# remote_unit_phase_3.net
KiCad netlist of a schematic drawn in EAGLE
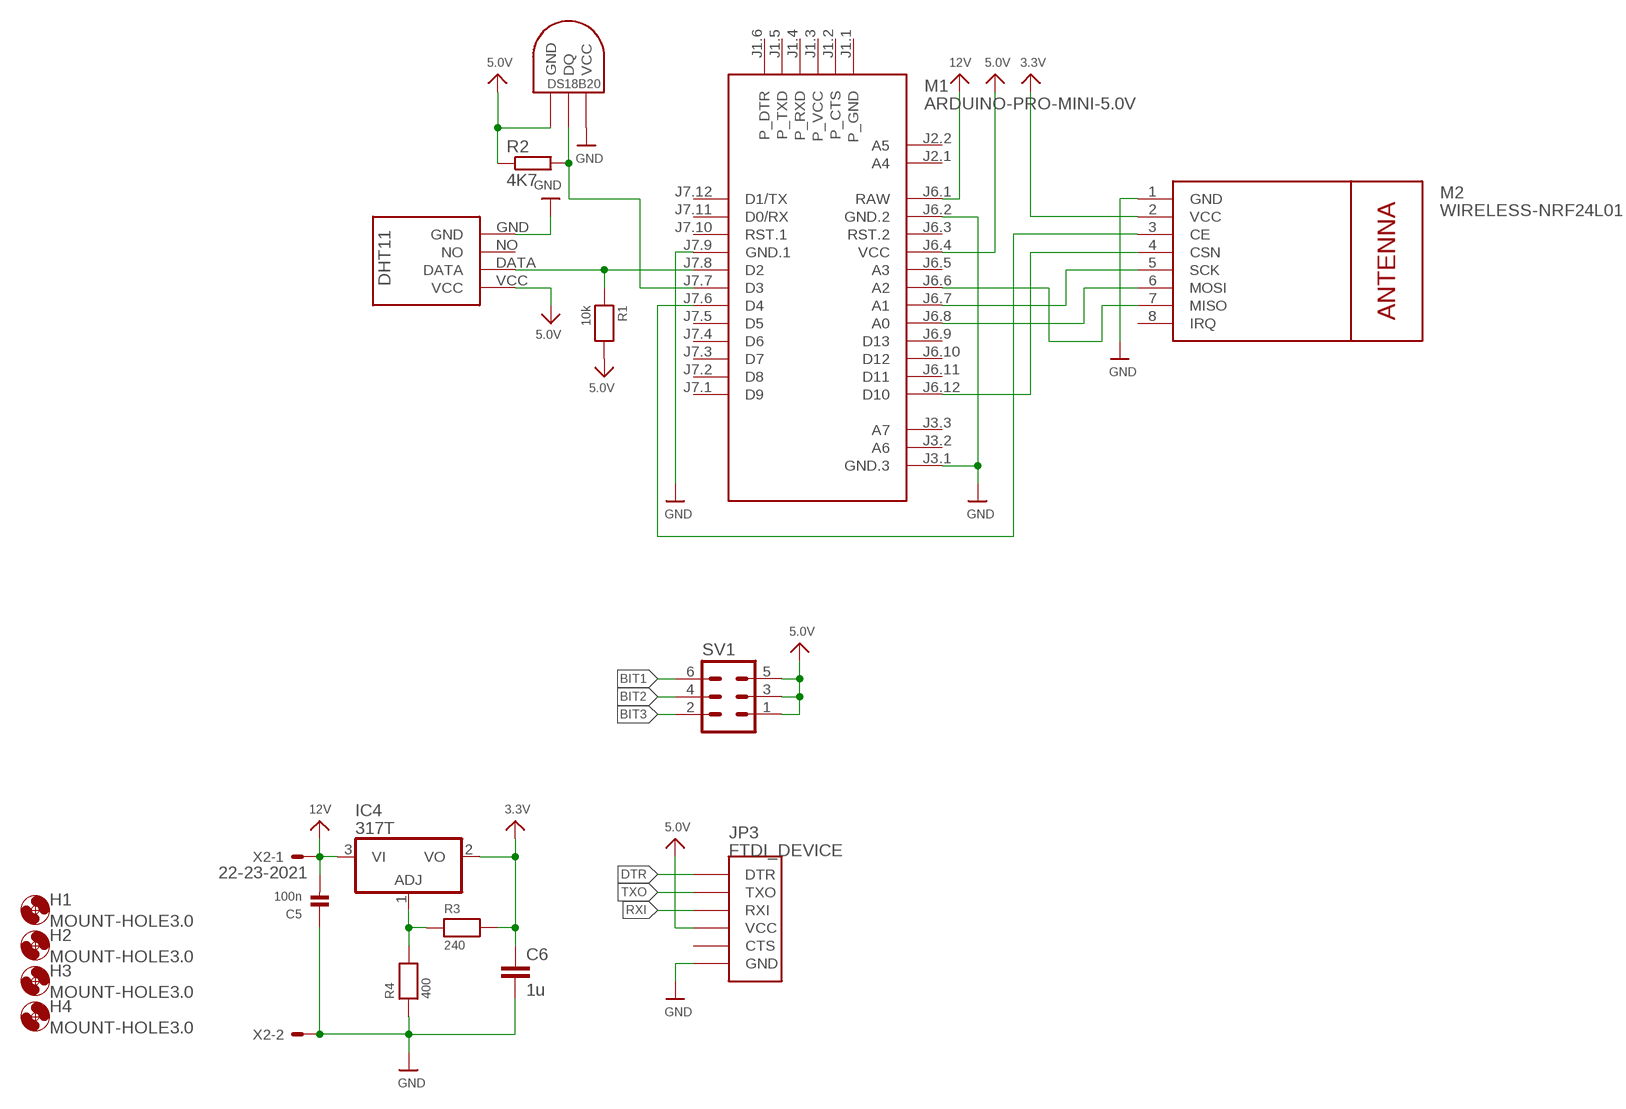
[diagram p0: schematic, sheet 1]

(export (version "E")
  (design (tool "Eeschema 10.0.6"))
  (components
    (comp (ref "C5")
      (value "100n")
      (footprint "eagle-import:_0603")
      (libsource (lib "eagle-import") (part "CAP_CERAMIC_0603"))
    )
    (comp (ref "C6")
      (value "1u")
      (footprint "eagle-import:C050-035X075")
      (libsource (lib "eagle-import") (part "C-EU050-035X075"))
    )
    (comp (ref "H1")
      (value "MOUNT-HOLE3.0")
      (footprint "eagle-import:3,0")
      (libsource (lib "eagle-import") (part "MOUNT-HOLE3.0"))
    )
    (comp (ref "H2")
      (value "MOUNT-HOLE3.0")
      (footprint "eagle-import:3,0")
      (libsource (lib "eagle-import") (part "MOUNT-HOLE3.0"))
    )
    (comp (ref "H3")
      (value "MOUNT-HOLE3.0")
      (footprint "eagle-import:3,0")
      (libsource (lib "eagle-import") (part "MOUNT-HOLE3.0"))
    )
    (comp (ref "H4")
      (value "MOUNT-HOLE3.0")
      (footprint "eagle-import:3,0")
      (libsource (lib "eagle-import") (part "MOUNT-HOLE3.0"))
    )
    (comp (ref "IC4")
      (value "317T")
      (footprint "eagle-import:TO220H")
      (libsource (lib "eagle-import") (part "317T"))
    )
    (comp (ref "JP3")
      (value "FTDI_DEVICE")
      (footprint "eagle-import:FTDI_DEVICE_SIDE")
      (libsource (lib "eagle-import") (part "FTDI_DEVICE"))
    )
    (comp (ref "M1")
      (value "ARDUINO-PRO-MINI-5.0V")
      (footprint "eagle-import:ARDUINO-PRO-MINI")
      (libsource (lib "eagle-import") (part "ARDUINO-PRO-MINI-5.0V"))
    )
    (comp (ref "M2")
      (value "WIRELESS-NRF24L01")
      (footprint "eagle-import:WIRELESS-NRF24L01")
      (libsource (lib "eagle-import") (part "WIRELESS-NRF24L01"))
    )
    (comp (ref "R1")
      (value "10k")
      (footprint "eagle-import:_0603")
      (libsource (lib "eagle-import") (part "RESISTOR_0603"))
    )
    (comp (ref "R2")
      (value "4K7")
      (footprint "eagle-import:0204_5")
      (libsource (lib "eagle-import") (part "R-EU_0204/5"))
    )
    (comp (ref "R3")
      (value "240")
      (footprint "eagle-import:_0603")
      (libsource (lib "eagle-import") (part "RESISTOR_0603"))
    )
    (comp (ref "R4")
      (value "400")
      (footprint "eagle-import:_0603")
      (libsource (lib "eagle-import") (part "RESISTOR_0603"))
    )
    (comp (ref "SV1")
      (value "MA03-2")
      (footprint "eagle-import:MA03-2")
      (libsource (lib "eagle-import") (part "MA03-2"))
    )
    (comp (ref "U$6")
      (value "DHT11")
      (footprint "eagle-import:DHT11")
      (libsource (lib "eagle-import") (part "DHT11"))
    )
    (comp (ref "U$14")
      (value "DS1820TO92")
      (footprint "eagle-import:DS1820")
      (libsource (lib "eagle-import") (part "DS1820TO92"))
    )
    (comp (ref "X2")
      (value "22-23-2021")
      (footprint "eagle-import:22-23-2021")
      (fields (field (name "MF") "MOLEX"))
      (libsource (lib "eagle-import") (part "22-23-2021"))
    )
  )
  (nets
    (net (code "1") (name "3.3V") (class "Default")
      (node (ref "C6") (pin "1") (pinfunction "1_1") (pintype "passive"))
      (node (ref "IC4") (pin "2") (pinfunction "VO_2") (pintype "passive"))
      (node (ref "M2") (pin "2") (pinfunction "VCC_2") (pintype "power_in"))
      (node (ref "R3") (pin "2") (pinfunction "2_2") (pintype "passive"))
    )
    (net (code "2") (name "5.0V") (class "Default")
      (node (ref "JP3") (pin "P$4") (pinfunction "VCC_P$4") (pintype "bidirectional"))
      (node (ref "M1") (pin "J6.4") (pinfunction "VCC_J6.4") (pintype "power_in"))
      (node (ref "R1") (pin "2") (pinfunction "2_2") (pintype "passive"))
      (node (ref "R2") (pin "1") (pinfunction "1_1") (pintype "passive"))
      (node (ref "SV1") (pin "1") (pinfunction "1_1") (pintype "passive"))
      (node (ref "SV1") (pin "3") (pinfunction "3_3") (pintype "passive"))
      (node (ref "SV1") (pin "5") (pinfunction "5_5") (pintype "passive"))
      (node (ref "U$14") (pin "GND") (pinfunction "GND_GND") (pintype "power_in"))
      (node (ref "U$6") (pin "VCC") (pinfunction "VCC_VCC") (pintype "bidirectional"))
    )
    (net (code "3") (name "12V") (class "Default")
      (node (ref "C5") (pin "2") (pinfunction "P$2_2") (pintype "passive"))
      (node (ref "IC4") (pin "3") (pinfunction "VI_3") (pintype "input"))
      (node (ref "M1") (pin "J6.1") (pinfunction "RAW_J6.1") (pintype "power_in"))
      (node (ref "X2") (pin "1") (pinfunction "S_1") (pintype "passive"))
    )
    (net (code "4") (name "BIT1") (class "Default")
      (node (ref "SV1") (pin "6") (pinfunction "6_6") (pintype "passive"))
    )
    (net (code "5") (name "BIT2") (class "Default")
      (node (ref "SV1") (pin "4") (pinfunction "4_4") (pintype "passive"))
    )
    (net (code "6") (name "BIT3") (class "Default")
      (node (ref "SV1") (pin "2") (pinfunction "2_2") (pintype "passive"))
    )
    (net (code "7") (name "DTR") (class "Default")
      (node (ref "JP3") (pin "P$1") (pinfunction "DTR_P$1") (pintype "bidirectional"))
    )
    (net (code "8") (name "GND") (class "Default")
      (node (ref "C5") (pin "1") (pinfunction "P$1_1") (pintype "passive"))
      (node (ref "C6") (pin "2") (pinfunction "2_2") (pintype "passive"))
      (node (ref "JP3") (pin "P$6") (pinfunction "GND_P$6") (pintype "bidirectional"))
      (node (ref "M1") (pin "J3.1") (pinfunction "GND.3_J3.1") (pintype "bidirectional"))
      (node (ref "M1") (pin "J6.2") (pinfunction "GND.2_J6.2") (pintype "power_in"))
      (node (ref "M1") (pin "J7.9") (pinfunction "GND.1_J7.9") (pintype "power_in"))
      (node (ref "M2") (pin "1") (pinfunction "GND_1") (pintype "power_in"))
      (node (ref "R4") (pin "1") (pinfunction "1_1") (pintype "passive"))
      (node (ref "U$14") (pin "VDD") (pinfunction "VCC_VDD") (pintype "power_in"))
      (node (ref "U$6") (pin "GND") (pinfunction "GND_GND") (pintype "bidirectional"))
      (node (ref "X2") (pin "2") (pinfunction "S_2") (pintype "passive"))
    )
    (net (code "9") (name "Net-(IC4-ADJ)") (class "Default")
      (node (ref "IC4") (pin "1") (pinfunction "ADJ_1") (pintype "input"))
      (node (ref "R3") (pin "1") (pinfunction "1_1") (pintype "passive"))
      (node (ref "R4") (pin "2") (pinfunction "2_2") (pintype "passive"))
    )
    (net (code "10") (name "Net-(M1-A0)") (class "Default")
      (node (ref "M1") (pin "J6.8") (pinfunction "A0_J6.8") (pintype "bidirectional"))
      (node (ref "M2") (pin "6") (pinfunction "MOSI_6") (pintype "bidirectional"))
    )
    (net (code "11") (name "Net-(M1-A1)") (class "Default")
      (node (ref "M1") (pin "J6.7") (pinfunction "A1_J6.7") (pintype "bidirectional"))
      (node (ref "M2") (pin "5") (pinfunction "SCK_5") (pintype "bidirectional"))
    )
    (net (code "12") (name "Net-(M1-A2)") (class "Default")
      (node (ref "M1") (pin "J6.6") (pinfunction "A2_J6.6") (pintype "bidirectional"))
      (node (ref "M2") (pin "7") (pinfunction "MISO_7") (pintype "bidirectional"))
    )
    (net (code "13") (name "Net-(M1-D2)") (class "Default")
      (node (ref "M1") (pin "J7.8") (pinfunction "D2_J7.8") (pintype "bidirectional"))
      (node (ref "R1") (pin "1") (pinfunction "1_1") (pintype "passive"))
      (node (ref "U$6") (pin "DATA") (pinfunction "DATA_DATA") (pintype "bidirectional"))
    )
    (net (code "14") (name "Net-(M1-D3)") (class "Default")
      (node (ref "M1") (pin "J7.7") (pinfunction "D3_J7.7") (pintype "bidirectional"))
      (node (ref "R2") (pin "2") (pinfunction "2_2") (pintype "passive"))
      (node (ref "U$14") (pin "DQ") (pinfunction "DQ_DQ") (pintype "bidirectional"))
    )
    (net (code "15") (name "Net-(M1-D4)") (class "Default")
      (node (ref "M1") (pin "J7.6") (pinfunction "D4_J7.6") (pintype "bidirectional"))
      (node (ref "M2") (pin "3") (pinfunction "CE_3") (pintype "bidirectional"))
    )
    (net (code "16") (name "Net-(M1-D10)") (class "Default")
      (node (ref "M1") (pin "J6.12") (pinfunction "D10_J6.12") (pintype "bidirectional"))
      (node (ref "M2") (pin "4") (pinfunction "CSN_4") (pintype "bidirectional"))
    )
    (net (code "17") (name "RXI") (class "Default")
      (node (ref "JP3") (pin "P$3") (pinfunction "RXI_P$3") (pintype "bidirectional"))
    )
    (net (code "18") (name "TXO") (class "Default")
      (node (ref "JP3") (pin "P$2") (pinfunction "TXO_P$2") (pintype "bidirectional"))
    )
    (net (code "19") (name "unconnected-(JP3-CTS-PadP$5)") (class "Default")
      (node (ref "JP3") (pin "P$5") (pinfunction "CTS_P$5") (pintype "bidirectional"))
    )
    (net (code "20") (name "unconnected-(M1-A3-PadJ6.5)") (class "Default")
      (node (ref "M1") (pin "J6.5") (pinfunction "A3_J6.5") (pintype "bidirectional"))
    )
    (net (code "21") (name "unconnected-(M1-A4-PadJ2.1)") (class "Default")
      (node (ref "M1") (pin "J2.1") (pinfunction "A4_J2.1") (pintype "bidirectional"))
    )
    (net (code "22") (name "unconnected-(M1-A5-PadJ2.2)") (class "Default")
      (node (ref "M1") (pin "J2.2") (pinfunction "A5_J2.2") (pintype "bidirectional"))
    )
    (net (code "23") (name "unconnected-(M1-A6-PadJ3.2)") (class "Default")
      (node (ref "M1") (pin "J3.2") (pinfunction "A6_J3.2") (pintype "bidirectional"))
    )
    (net (code "24") (name "unconnected-(M1-A7-PadJ3.3)") (class "Default")
      (node (ref "M1") (pin "J3.3") (pinfunction "A7_J3.3") (pintype "bidirectional"))
    )
    (net (code "25") (name "unconnected-(M1-D0{slash}RX-PadJ7.11)") (class "Default")
      (node (ref "M1") (pin "J7.11") (pinfunction "D0/RX_J7.11") (pintype "bidirectional"))
    )
    (net (code "26") (name "unconnected-(M1-D1{slash}TX-PadJ7.12)") (class "Default")
      (node (ref "M1") (pin "J7.12") (pinfunction "D1/TX_J7.12") (pintype "bidirectional"))
    )
    (net (code "27") (name "unconnected-(M1-D5-PadJ7.5)") (class "Default")
      (node (ref "M1") (pin "J7.5") (pinfunction "D5_J7.5") (pintype "bidirectional"))
    )
    (net (code "28") (name "unconnected-(M1-D6-PadJ7.4)") (class "Default")
      (node (ref "M1") (pin "J7.4") (pinfunction "D6_J7.4") (pintype "bidirectional"))
    )
    (net (code "29") (name "unconnected-(M1-D7-PadJ7.3)") (class "Default")
      (node (ref "M1") (pin "J7.3") (pinfunction "D7_J7.3") (pintype "bidirectional"))
    )
    (net (code "30") (name "unconnected-(M1-D8-PadJ7.2)") (class "Default")
      (node (ref "M1") (pin "J7.2") (pinfunction "D8_J7.2") (pintype "bidirectional"))
    )
    (net (code "31") (name "unconnected-(M1-D9-PadJ7.1)") (class "Default")
      (node (ref "M1") (pin "J7.1") (pinfunction "D9_J7.1") (pintype "bidirectional"))
    )
    (net (code "32") (name "unconnected-(M1-D11-PadJ6.11)") (class "Default")
      (node (ref "M1") (pin "J6.11") (pinfunction "D11_J6.11") (pintype "bidirectional"))
    )
    (net (code "33") (name "unconnected-(M1-D12-PadJ6.10)") (class "Default")
      (node (ref "M1") (pin "J6.10") (pinfunction "D12_J6.10") (pintype "bidirectional"))
    )
    (net (code "34") (name "unconnected-(M1-D13-PadJ6.9)") (class "Default")
      (node (ref "M1") (pin "J6.9") (pinfunction "D13_J6.9") (pintype "bidirectional"))
    )
    (net (code "35") (name "unconnected-(M1-P_CTS-PadJ1.2)") (class "Default")
      (node (ref "M1") (pin "J1.2") (pinfunction "P_CTS_J1.2") (pintype "bidirectional"))
    )
    (net (code "36") (name "unconnected-(M1-P_DTR-PadJ1.6)") (class "Default")
      (node (ref "M1") (pin "J1.6") (pinfunction "P_DTR_J1.6") (pintype "bidirectional"))
    )
    (net (code "37") (name "unconnected-(M1-P_GND-PadJ1.1)") (class "Default")
      (node (ref "M1") (pin "J1.1") (pinfunction "P_GND_J1.1") (pintype "bidirectional"))
    )
    (net (code "38") (name "unconnected-(M1-P_RXD-PadJ1.4)") (class "Default")
      (node (ref "M1") (pin "J1.4") (pinfunction "P_RXD_J1.4") (pintype "bidirectional"))
    )
    (net (code "39") (name "unconnected-(M1-P_TXD-PadJ1.5)") (class "Default")
      (node (ref "M1") (pin "J1.5") (pinfunction "P_TXD_J1.5") (pintype "bidirectional"))
    )
    (net (code "40") (name "unconnected-(M1-P_VCC-PadJ1.3)") (class "Default")
      (node (ref "M1") (pin "J1.3") (pinfunction "P_VCC_J1.3") (pintype "bidirectional"))
    )
    (net (code "41") (name "unconnected-(M1-RST.1-PadJ7.10)") (class "Default")
      (node (ref "M1") (pin "J7.10") (pinfunction "RST.1_J7.10") (pintype "bidirectional"))
    )
    (net (code "42") (name "unconnected-(M1-RST.2-PadJ6.3)") (class "Default")
      (node (ref "M1") (pin "J6.3") (pinfunction "RST.2_J6.3") (pintype "bidirectional"))
    )
    (net (code "43") (name "unconnected-(M2-IRQ-Pad8)") (class "Default")
      (node (ref "M2") (pin "8") (pinfunction "IRQ_8") (pintype "bidirectional"))
    )
    (net (code "44") (name "unconnected-(U$6-PadNO)") (class "Default")
      (node (ref "U$6") (pin "NO") (pinfunction "NO_NO") (pintype "bidirectional"))
    )
  )
)
